# currentDriver.net
KiCad netlist of a schematic drawn in Altium Designer
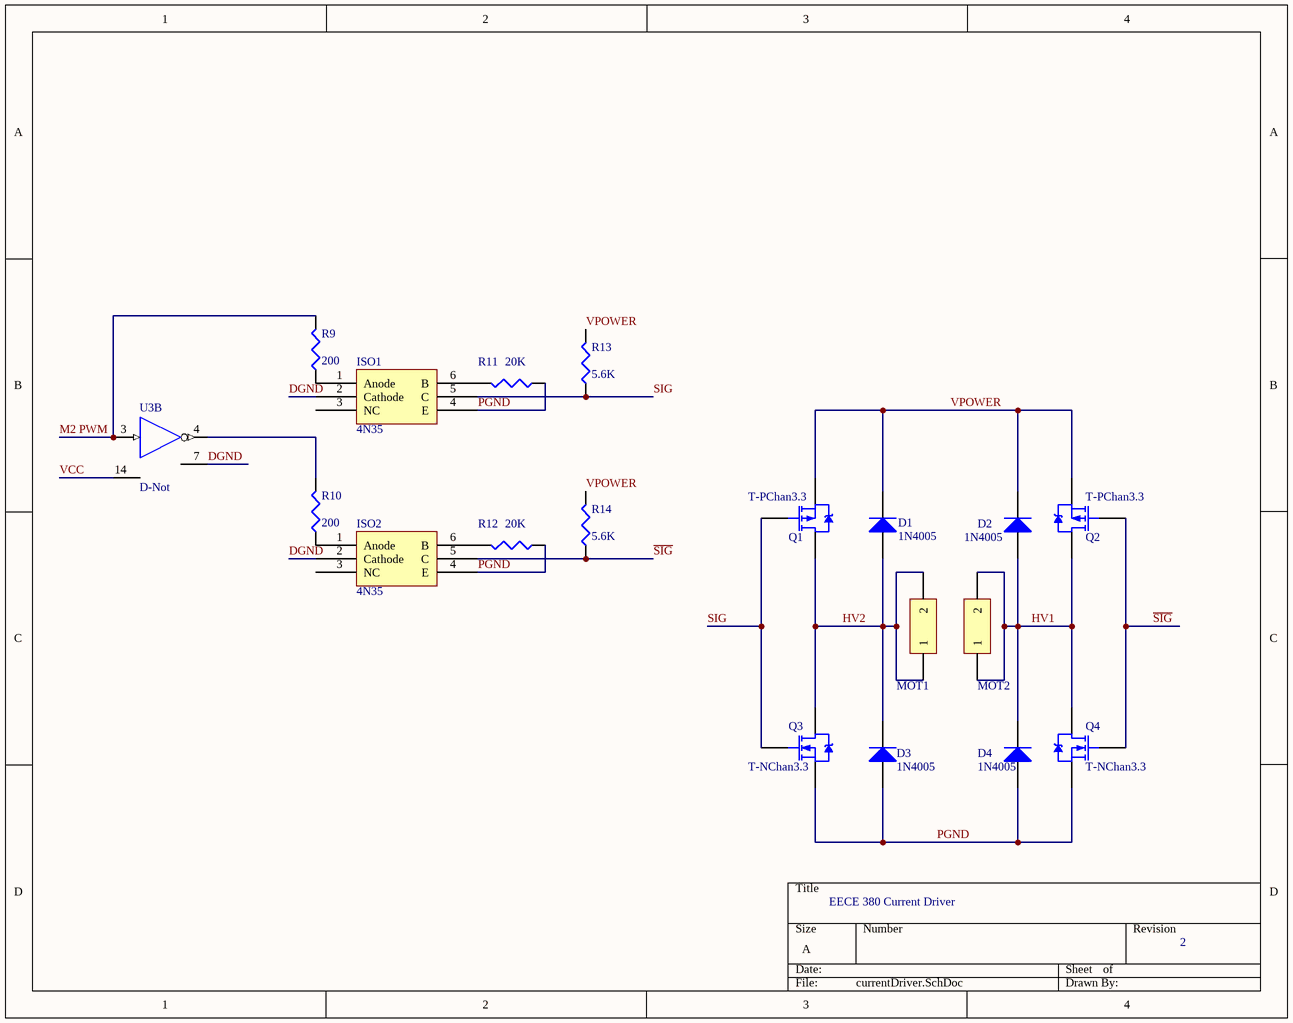
[diagram p0: currentDriver.SchDoc]

(export (version "E")
  (design (tool "Eeschema 10.0.6"))
  (components
    (comp (ref "D1")
      (value "1N4005")
      (footprint "DO-41_XLGE1.2")
      (description "diode")
      (fields (field (name "PUBLISHER") "Altium Limited"))
      (libsource (lib "PartsDatabaseV12") (part "T-Diode-1N4005"))
    )
    (comp (ref "D2")
      (value "1N4005")
      (footprint "DO-41_XLGE1.2")
      (description "diode")
      (fields (field (name "PUBLISHER") "Altium Limited"))
      (libsource (lib "PartsDatabaseV12") (part "T-Diode-1N4005"))
    )
    (comp (ref "D3")
      (value "1N4005")
      (footprint "DO-41_XLGE1.2")
      (description "diode")
      (fields (field (name "PUBLISHER") "Altium Limited"))
      (libsource (lib "PartsDatabaseV12") (part "T-Diode-1N4005"))
    )
    (comp (ref "D4")
      (value "1N4005")
      (footprint "DO-41_XLGE1.2")
      (description "diode")
      (fields (field (name "PUBLISHER") "Altium Limited"))
      (libsource (lib "PartsDatabaseV12") (part "T-Diode-1N4005"))
    )
    (comp (ref "ISO1")
      (value "4N35")
      (footprint "DIP6LGE")
      (libsource (lib "controllerSchLib") (part "4N35"))
    )
    (comp (ref "ISO2")
      (value "4N35")
      (footprint "DIP6LGE")
      (libsource (lib "controllerSchLib") (part "4N35"))
    )
    (comp (ref "MOT1")
      (value "C-Ban")
      (footprint "Ban1cm_2XLGE1.5")
      (description "Banana plug fem")
      (fields (field (name "PUBLISHER") "Altium Limited"))
      (libsource (lib "PartsDatabaseV13p1") (part "C-Ban"))
    )
    (comp (ref "MOT2")
      (value "Ban")
      (footprint "Ban1cm_2XLGE1.5")
      (description "Banana plug fem")
      (fields (field (name "PUBLISHER") "Altium Limited"))
      (libsource (lib "PartsDatabaseV13p1") (part "C-Ban"))
    )
    (comp (ref "Q1")
      (value "T-PChan3.3")
      (footprint "TO-220AB")
      (description "P-Channel Power MOSFET")
      (libsource (lib "PartsDatabaseV13p1") (part "T-PChan3.3"))
    )
    (comp (ref "Q2")
      (value "T-PChan3.3")
      (footprint "TO-220AB")
      (description "P-Channel Power MOSFET")
      (libsource (lib "PartsDatabaseV13p1") (part "T-PChan3.3"))
    )
    (comp (ref "Q3")
      (value "T-NChan3.3")
      (footprint "TO-220AB")
      (description "N-Channel Power MOSFET")
      (libsource (lib "PartsDatabaseV13p1") (part "T-NChan3.3"))
    )
    (comp (ref "Q4")
      (value "T-NChan3.3")
      (footprint "TO-220AB")
      (description "N-Channel Power MOSFET")
      (libsource (lib "PartsDatabaseV13p1") (part "T-NChan3.3"))
    )
    (comp (ref "R9")
      (value "200")
      (footprint "Res10mm_LGE1.0")
      (description "resistor (specify value)")
      (fields (field (name "Comment") "-Res") (field (name "PUBLISHER") "Altium Limited"))
      (libsource (lib "PartsDatabaseV13p1") (part "G-Res"))
    )
    (comp (ref "R10")
      (value "200")
      (footprint "Res10mm_LGE1.0")
      (description "resistor (specify value)")
      (fields (field (name "PUBLISHER") "Altium Limited"))
      (libsource (lib "PartsDatabaseV13p1") (part "G-Res"))
    )
    (comp (ref "R11")
      (value "20K")
      (footprint "Res10mm_LGE1.0")
      (description "resistor (specify value)")
      (fields (field (name "Comment") "G-Res") (field (name "PUBLISHER") "Altium Limited"))
      (libsource (lib "PartsDatabaseV13p1") (part "G-Res"))
    )
    (comp (ref "R12")
      (value "20K")
      (footprint "Res10mm_LGE1.0")
      (description "resistor (specify value)")
      (fields (field (name "Comment") "G-Res") (field (name "PUBLISHER") "Altium Limited"))
      (libsource (lib "PartsDatabaseV13p1") (part "G-Res"))
    )
    (comp (ref "R13")
      (value "5.6K")
      (footprint "Res10mm_LGE1.0")
      (description "resistor (specify value)")
      (fields (field (name "Comment") "G-Res") (field (name "PUBLISHER") "Altium Limited"))
      (libsource (lib "PartsDatabaseV13p1") (part "G-Res"))
    )
    (comp (ref "R14")
      (value "5.6K")
      (footprint "Res10mm_LGE1.0")
      (description "resistor (specify value)")
      (fields (field (name "Comment") "G-Res") (field (name "PUBLISHER") "Altium Limited"))
      (libsource (lib "PartsDatabaseV13p1") (part "G-Res"))
    )
    (comp (ref "U3")
      (value "D-Not")
      (footprint "DIP14_LGE1.0")
      (description "hex NOT gate (inverter)")
      (fields (field (name "PUBLISHER") "Altium Limited"))
      (libsource (lib "PartsDatabaseV13p1") (part "D-Not"))
    )
  )
  (nets
    (net (code "1") (name "/DGND") (class "Default")
      (node (ref "ISO1") (pin "2") (pinfunction "Cathode_2") (pintype "passive"))
      (node (ref "ISO2") (pin "2") (pinfunction "Cathode_2") (pintype "passive"))
      (node (ref "U3") (pin "7") (pinfunction "GND_7") (pintype "power_in"))
    )
    (net (code "2") (name "/HV1") (class "Default")
      (node (ref "D2") (pin "1") (pinfunction "A_1") (pintype "passive"))
      (node (ref "D4") (pin "2") (pinfunction "K_2") (pintype "passive"))
      (node (ref "MOT2") (pin "1") (pinfunction "1_1") (pintype "passive"))
      (node (ref "MOT2") (pin "2") (pinfunction "2_2") (pintype "passive"))
      (node (ref "Q2") (pin "2") (pinfunction "D_2") (pintype "passive"))
      (node (ref "Q4") (pin "2") (pinfunction "D_2") (pintype "passive"))
    )
    (net (code "3") (name "/HV2") (class "Default")
      (node (ref "D1") (pin "1") (pinfunction "A_1") (pintype "passive"))
      (node (ref "D3") (pin "2") (pinfunction "K_2") (pintype "passive"))
      (node (ref "MOT1") (pin "1") (pinfunction "1_1") (pintype "passive"))
      (node (ref "MOT1") (pin "2") (pinfunction "2_2") (pintype "passive"))
      (node (ref "Q1") (pin "2") (pinfunction "D_2") (pintype "passive"))
      (node (ref "Q3") (pin "2") (pinfunction "D_2") (pintype "passive"))
    )
    (net (code "4") (name "/M2 PWM") (class "Default")
      (node (ref "R9") (pin "2") (pinfunction "2_2") (pintype "passive"))
      (node (ref "U3") (pin "3") (pinfunction "A_3") (pintype "input"))
    )
    (net (code "5") (name "/PGND") (class "Default")
      (node (ref "D3") (pin "1") (pinfunction "A_1") (pintype "passive"))
      (node (ref "D4") (pin "1") (pinfunction "A_1") (pintype "passive"))
      (node (ref "ISO1") (pin "4") (pinfunction "E_4") (pintype "passive"))
      (node (ref "ISO2") (pin "4") (pinfunction "E_4") (pintype "passive"))
      (node (ref "Q3") (pin "3") (pinfunction "S_3") (pintype "passive"))
      (node (ref "Q4") (pin "3") (pinfunction "S_3") (pintype "passive"))
      (node (ref "R11") (pin "1") (pinfunction "1_1") (pintype "passive"))
      (node (ref "R12") (pin "1") (pinfunction "1_1") (pintype "passive"))
    )
    (net (code "6") (name "/SIG") (class "Default")
      (node (ref "ISO1") (pin "5") (pinfunction "C_5") (pintype "passive"))
      (node (ref "Q1") (pin "1") (pinfunction "G_1") (pintype "passive"))
      (node (ref "Q3") (pin "1") (pinfunction "G_1") (pintype "passive"))
      (node (ref "R13") (pin "1") (pinfunction "1_1") (pintype "passive"))
    )
    (net (code "7") (name "/VCC") (class "Default")
      (node (ref "U3") (pin "14") (pinfunction "VCC_14") (pintype "power_in"))
    )
    (net (code "8") (name "/VPOWER") (class "Default")
      (node (ref "D1") (pin "2") (pinfunction "K_2") (pintype "passive"))
      (node (ref "D2") (pin "2") (pinfunction "K_2") (pintype "passive"))
      (node (ref "Q1") (pin "3") (pinfunction "S_3") (pintype "passive"))
      (node (ref "Q2") (pin "3") (pinfunction "S_3") (pintype "passive"))
      (node (ref "R13") (pin "2") (pinfunction "2_2") (pintype "passive"))
      (node (ref "R14") (pin "2") (pinfunction "2_2") (pintype "passive"))
    )
    (net (code "9") (name "/~{SIG}") (class "Default")
      (node (ref "ISO2") (pin "5") (pinfunction "C_5") (pintype "passive"))
      (node (ref "Q2") (pin "1") (pinfunction "G_1") (pintype "passive"))
      (node (ref "Q4") (pin "1") (pinfunction "G_1") (pintype "passive"))
      (node (ref "R14") (pin "1") (pinfunction "1_1") (pintype "passive"))
    )
    (net (code "10") (name "Net-(ISO1-Anode)") (class "Default")
      (node (ref "ISO1") (pin "1") (pinfunction "Anode_1") (pintype "passive"))
      (node (ref "R9") (pin "1") (pinfunction "1_1") (pintype "passive"))
    )
    (net (code "11") (name "Net-(ISO1-B)") (class "Default")
      (node (ref "ISO1") (pin "6") (pinfunction "B_6") (pintype "passive"))
      (node (ref "R11") (pin "2") (pinfunction "2_2") (pintype "passive"))
    )
    (net (code "12") (name "Net-(ISO2-Anode)") (class "Default")
      (node (ref "ISO2") (pin "1") (pinfunction "Anode_1") (pintype "passive"))
      (node (ref "R10") (pin "1") (pinfunction "1_1") (pintype "passive"))
    )
    (net (code "13") (name "Net-(ISO2-B)") (class "Default")
      (node (ref "ISO2") (pin "6") (pinfunction "B_6") (pintype "passive"))
      (node (ref "R12") (pin "2") (pinfunction "2_2") (pintype "passive"))
    )
    (net (code "14") (name "Net-(U3B-Y)") (class "Default")
      (node (ref "R10") (pin "2") (pinfunction "2_2") (pintype "passive"))
      (node (ref "U3") (pin "4") (pinfunction "Y_4") (pintype "output"))
    )
    (net (code "15") (name "unconnected-(ISO1-NC-Pad3)") (class "Default")
      (node (ref "ISO1") (pin "3") (pinfunction "NC_3") (pintype "passive"))
    )
    (net (code "16") (name "unconnected-(ISO2-NC-Pad3)") (class "Default")
      (node (ref "ISO2") (pin "3") (pinfunction "NC_3") (pintype "passive"))
    )
  )
)
